# LED0805_v1_0.net
KiCad netlist of a schematic drawn in Altium Designer
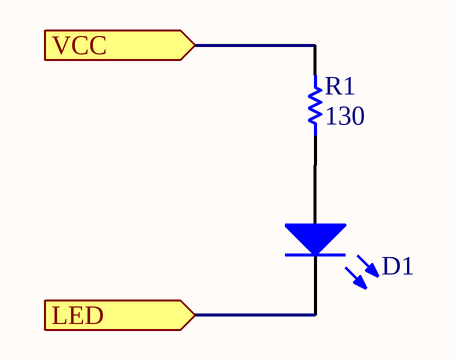
[diagram p0: LED0805_v1.0.SchDoc]

(export (version "E")
  (design (tool "Eeschema 10.0.6"))
  (components
    (comp (ref "D1")
      (value "LED - NORMAL LED")
      (footprint "LED-0805 BLUE")
      (libsource (lib "CHINOOK_LIBRARY") (part "LED - NORMAL LED"))
    )
    (comp (ref "R1")
      (value "130")
      (footprint "RS-0603")
      (fields
        (field (name "TOLERANCE") "RES TOL")
        (field (name "POWER") "RES POWER")
        (field (name "Comment") "RS - RESISTOR")
      )
      (libsource (lib "CHINOOK_LIBRARY") (part "RS - RESISTOR"))
    )
  )
  (nets
    (net (code "1") (name "/LED") (class "Default")
      (node (ref "D1") (pin "K") (pinfunction "K_K") (pintype "passive"))
    )
    (net (code "2") (name "/VCC") (class "Default")
      (node (ref "R1") (pin "2") (pinfunction "2_2") (pintype "passive"))
    )
    (net (code "3") (name "Net-(D1-PadA)") (class "Default")
      (node (ref "D1") (pin "A") (pinfunction "A_A") (pintype "passive"))
      (node (ref "R1") (pin "1") (pinfunction "1_1") (pintype "passive"))
    )
  )
)
